# Audio.net
KiCad netlist of a schematic drawn in Altium Designer
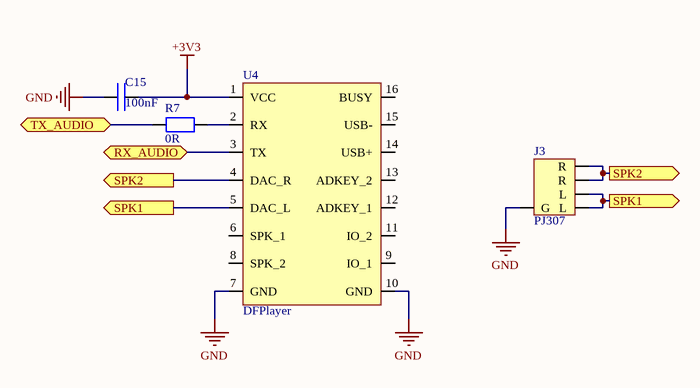
[diagram p0: Audio.SchDoc]

(export (version "E")
  (design (tool "Eeschema 10.0.6"))
  (components
    (comp (ref "C15") (value "100nF") (footprint "C0603") (libsource (lib "przem_lib") (part "Cap_SMD")))
    (comp (ref "J3")
      (value "PJ307")
      (footprint "PJ307")
      (libsource (lib "przem_lib") (part "Jack_3.5mm_PJ307"))
    )
    (comp (ref "R7") (value "0R") (footprint "R0603") (libsource (lib "przem_lib") (part "Res")))
    (comp (ref "U4")
      (value "DFPlayer")
      (footprint "DFPLAYER")
      (libsource (lib "przem_lib") (part "DFPlayer"))
    )
  )
  (nets
    (net (code "1") (name "+3V3") (class "Default")
      (node (ref "C15") (pin "2") (pinfunction "2_2") (pintype "passive"))
      (node (ref "U4") (pin "1") (pinfunction "VCC_1") (pintype "passive"))
    )
    (net (code "2") (name "/RX_AUDIO") (class "Default")
      (node (ref "U4") (pin "3") (pinfunction "TX_3") (pintype "passive"))
    )
    (net (code "3") (name "/SPK1") (class "Default")
      (node (ref "J3") (pin "2") (pinfunction "L_2") (pintype "passive"))
      (node (ref "J3") (pin "3") (pinfunction "L_3") (pintype "passive"))
      (node (ref "U4") (pin "5") (pinfunction "DAC_L_5") (pintype "passive"))
    )
    (net (code "4") (name "/SPK2") (class "Default")
      (node (ref "J3") (pin "4") (pinfunction "R_4") (pintype "passive"))
      (node (ref "J3") (pin "5") (pinfunction "R_5") (pintype "passive"))
      (node (ref "U4") (pin "4") (pinfunction "DAC_R_4") (pintype "passive"))
    )
    (net (code "5") (name "/TX_AUDIO") (class "Default")
      (node (ref "R7") (pin "1") (pinfunction "1_1") (pintype "passive"))
    )
    (net (code "6") (name "GND") (class "Default")
      (node (ref "C15") (pin "1") (pinfunction "1_1") (pintype "passive"))
      (node (ref "J3") (pin "1") (pinfunction "G_1") (pintype "passive"))
      (node (ref "U4") (pin "10") (pinfunction "GND_10") (pintype "passive"))
      (node (ref "U4") (pin "7") (pinfunction "GND_7") (pintype "passive"))
    )
    (net (code "7") (name "Net-(U4-RX)") (class "Default")
      (node (ref "R7") (pin "2") (pinfunction "2_2") (pintype "passive"))
      (node (ref "U4") (pin "2") (pinfunction "RX_2") (pintype "passive"))
    )
    (net (code "8") (name "unconnected-(U4-ADKEY_1-Pad12)") (class "Default")
      (node (ref "U4") (pin "12") (pinfunction "ADKEY_1_12") (pintype "passive"))
    )
    (net (code "9") (name "unconnected-(U4-ADKEY_2-Pad13)") (class "Default")
      (node (ref "U4") (pin "13") (pinfunction "ADKEY_2_13") (pintype "passive"))
    )
    (net (code "10") (name "unconnected-(U4-BUSY-Pad16)") (class "Default")
      (node (ref "U4") (pin "16") (pinfunction "BUSY_16") (pintype "passive"))
    )
    (net (code "11") (name "unconnected-(U4-IO_1-Pad9)") (class "Default")
      (node (ref "U4") (pin "9") (pinfunction "IO_1_9") (pintype "passive"))
    )
    (net (code "12") (name "unconnected-(U4-IO_2-Pad11)") (class "Default")
      (node (ref "U4") (pin "11") (pinfunction "IO_2_11") (pintype "passive"))
    )
    (net (code "13") (name "unconnected-(U4-SPK_1-Pad6)") (class "Default")
      (node (ref "U4") (pin "6") (pinfunction "SPK_1_6") (pintype "passive"))
    )
    (net (code "14") (name "unconnected-(U4-SPK_2-Pad8)") (class "Default")
      (node (ref "U4") (pin "8") (pinfunction "SPK_2_8") (pintype "passive"))
    )
    (net (code "15") (name "unconnected-(U4-USB+-Pad14)") (class "Default")
      (node (ref "U4") (pin "14") (pinfunction "USB+_14") (pintype "passive"))
    )
    (net (code "16") (name "unconnected-(U4-USB--Pad15)") (class "Default")
      (node (ref "U4") (pin "15") (pinfunction "USB-_15") (pintype "passive"))
    )
  )
)
